# FPGA.net
KiCad netlist of a schematic drawn in Altium Designer
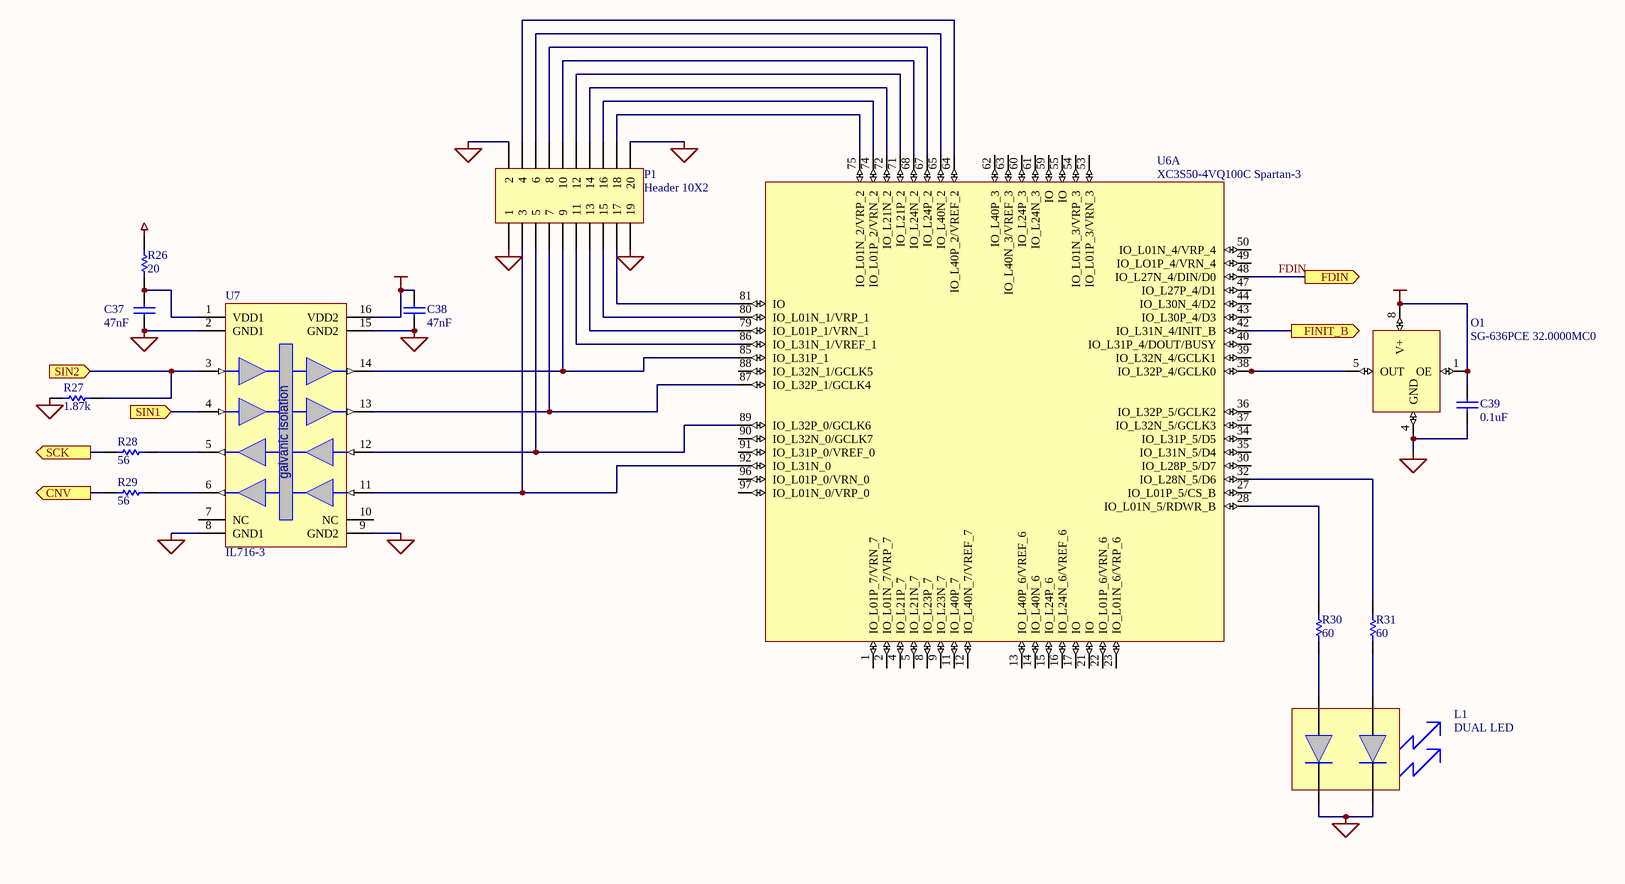
[diagram p0: FPGA.SCHDOC]

(export (version "E")
  (design (tool "Eeschema 10.0.6"))
  (components
    (comp (ref "C37")
      (value "47nF")
      (footprint "CC1608-0603")
      (description "Capacitor")
      (fields
        (field (name "MANUFACTURER") "Generic Components")
        (field (name "Comment") "Cap")
        (field (name "PUBLISHER") "Altium Limited")
      )
      (libsource (lib "Miscellaneous Devices") (part "Cap"))
    )
    (comp (ref "C38")
      (value "47nF")
      (footprint "CC1608-0603")
      (description "Capacitor")
      (fields
        (field (name "MANUFACTURER") "Generic Components")
        (field (name "Comment") "Cap")
        (field (name "PUBLISHER") "Altium Limited")
      )
      (libsource (lib "Miscellaneous Devices") (part "Cap"))
    )
    (comp (ref "C39")
      (value "0.1uF")
      (footprint "CC1608-0603")
      (description "Capacitor")
      (fields
        (field (name "MANUFACTURER") "Generic Components")
        (field (name "Comment") "Cap")
        (field (name "PUBLISHER") "Altium Limited")
      )
      (libsource (lib "Miscellaneous Devices") (part "Cap"))
    )
    (comp (ref "L1")
      (value "DUAL LED")
      (footprint "LUMEX DUAL RT-ANG LED")
      (libsource (lib "parts") (part "DUAL LED"))
    )
    (comp (ref "O1")
      (value "SG-636PCE 32.0000MC0")
      (footprint "SG636PCE")
      (description "Epson CMOS/TTL Oscillator")
      (libsource (lib "parts") (part "SG-636PCE"))
    )
    (comp (ref "P1")
      (value "Header 10X2")
      (footprint "HDR2X10")
      (description "Header, 10-Pin, Dual row")
      (fields (field (name "PUBLISHER") "Altium Limited"))
      (libsource (lib "Miscellaneous Connectors") (part "Header 10X2"))
    )
    (comp (ref "R26")
      (value "20")
      (footprint "CC1608-0603")
      (description "Resistor")
      (fields
        (field (name "MANUFACTURER") "Generic Components")
        (field (name "Comment") "Res1")
        (field (name "PUBLISHER") "Altium Limited")
      )
      (libsource (lib "Miscellaneous Devices") (part "Res1"))
    )
    (comp (ref "R27")
      (value "1.87k")
      (footprint "CC1608-0603")
      (description "Resistor")
      (fields
        (field (name "MANUFACTURER") "Generic Components")
        (field (name "Comment") "Res1")
        (field (name "PUBLISHER") "Altium Limited")
      )
      (libsource (lib "Miscellaneous Devices") (part "Res1"))
    )
    (comp (ref "R28")
      (value "56")
      (footprint "CC1608-0603")
      (description "Resistor")
      (fields
        (field (name "MANUFACTURER") "Generic Components")
        (field (name "Comment") "Res1")
        (field (name "PUBLISHER") "Altium Limited")
      )
      (libsource (lib "Miscellaneous Devices") (part "Res1"))
    )
    (comp (ref "R29")
      (value "56")
      (footprint "CC1608-0603")
      (description "Resistor")
      (fields
        (field (name "MANUFACTURER") "Generic Components")
        (field (name "Comment") "Res1")
        (field (name "PUBLISHER") "Altium Limited")
      )
      (libsource (lib "Miscellaneous Devices") (part "Res1"))
    )
    (comp (ref "R30")
      (value "60")
      (footprint "CC1608-0603")
      (description "Resistor")
      (fields
        (field (name "MANUFACTURER") "Generic Components")
        (field (name "Comment") "Res1")
        (field (name "PUBLISHER") "Altium Limited")
      )
      (libsource (lib "Miscellaneous Devices") (part "Res1"))
    )
    (comp (ref "R31")
      (value "60")
      (footprint "CC1608-0603")
      (description "Resistor")
      (fields
        (field (name "MANUFACTURER") "Generic Components")
        (field (name "Comment") "Res1")
        (field (name "PUBLISHER") "Altium Limited")
      )
      (libsource (lib "Miscellaneous Devices") (part "Res1"))
    )
    (comp (ref "U6")
      (value "XC3S50-4VQ100C Spartan-3")
      (footprint "Xilinx TQ100")
      (description "Xilinx Spartan-3 VQ100")
      (libsource (lib "parts") (part "XC3S50-4VQ100C"))
    )
    (comp (ref "U7")
      (value "IL716-3")
      (footprint "SO-G16/D10")
      (description "High speed digital coupler")
      (libsource (lib "parts") (part "IL716-3"))
    )
  )
  (nets
    (net (code "1") (name "/CNV") (class "Default")
      (node (ref "R29") (pin "1") (pinfunction "1_1") (pintype "passive"))
    )
    (net (code "2") (name "/FDIN") (class "Default")
      (node (ref "U6") (pin "48") (pinfunction "IO_L27N_4/DIN/D0_48") (pintype "bidirectional"))
    )
    (net (code "3") (name "/FINIT_B") (class "Default")
      (node (ref "U6") (pin "42") (pinfunction "IO_L31N_4/INIT_B_42") (pintype "bidirectional"))
    )
    (net (code "4") (name "/SCK") (class "Default")
      (node (ref "R28") (pin "1") (pinfunction "1_1") (pintype "passive"))
    )
    (net (code "5") (name "/SIN1") (class "Default")
      (node (ref "U7") (pin "4") (pinfunction "IN2_4") (pintype "input"))
    )
    (net (code "6") (name "/SIN2") (class "Default")
      (node (ref "R27") (pin "2") (pinfunction "2_2") (pintype "passive"))
      (node (ref "U7") (pin "3") (pinfunction "IN1_3") (pintype "input"))
    )
    (net (code "7") (name "AGND") (class "Default")
      (node (ref "C37") (pin "1") (pinfunction "1_1") (pintype "passive"))
      (node (ref "R27") (pin "1") (pinfunction "1_1") (pintype "passive"))
      (node (ref "U7") (pin "2") (pinfunction "GND1_2") (pintype "power_in"))
      (node (ref "U7") (pin "8") (pinfunction "GND1_8") (pintype "power_in"))
    )
    (net (code "8") (name "AVDD") (class "Default")
      (node (ref "R26") (pin "2") (pinfunction "2_2") (pintype "passive"))
    )
    (net (code "9") (name "GND") (class "Default")
      (node (ref "C38") (pin "1") (pinfunction "1_1") (pintype "passive"))
      (node (ref "C39") (pin "2") (pinfunction "2_2") (pintype "passive"))
      (node (ref "L1") (pin "2") (pinfunction "2_2") (pintype "passive"))
      (node (ref "L1") (pin "4") (pinfunction "C2_4") (pintype "passive"))
      (node (ref "O1") (pin "4") (pinfunction "GND_4") (pintype "bidirectional"))
      (node (ref "P1") (pin "1") (pinfunction "1_1") (pintype "passive"))
      (node (ref "P1") (pin "19") (pinfunction "19_19") (pintype "passive"))
      (node (ref "P1") (pin "2") (pinfunction "2_2") (pintype "passive"))
      (node (ref "P1") (pin "20") (pinfunction "20_20") (pintype "passive"))
      (node (ref "U7") (pin "15") (pinfunction "GND2_15") (pintype "power_in"))
      (node (ref "U7") (pin "9") (pinfunction "GND2_9") (pintype "power_in"))
    )
    (net (code "10") (name "Net-(L1-A1)") (class "Default")
      (node (ref "L1") (pin "1") (pinfunction "A1_1") (pintype "passive"))
      (node (ref "R30") (pin "2") (pinfunction "2_2") (pintype "passive"))
    )
    (net (code "11") (name "Net-(L1-A2)") (class "Default")
      (node (ref "L1") (pin "3") (pinfunction "A2_3") (pintype "passive"))
      (node (ref "R31") (pin "2") (pinfunction "2_2") (pintype "passive"))
    )
    (net (code "12") (name "Net-(O1-OUT)") (class "Default")
      (node (ref "O1") (pin "5") (pinfunction "OUT_5") (pintype "bidirectional"))
      (node (ref "U6") (pin "38") (pinfunction "IO_L32P_4/GCLK0_38") (pintype "bidirectional"))
    )
    (net (code "13") (name "Net-(P1-Pad17)") (class "Default")
      (node (ref "P1") (pin "17") (pinfunction "17_17") (pintype "passive"))
      (node (ref "U6") (pin "81") (pinfunction "IO_81") (pintype "bidirectional"))
    )
    (net (code "14") (name "Net-(U6A-IO_L01N_1{slash}VRP_1)") (class "Default")
      (node (ref "P1") (pin "15") (pinfunction "15_15") (pintype "passive"))
      (node (ref "U6") (pin "80") (pinfunction "IO_L01N_1/VRP_1_80") (pintype "bidirectional"))
    )
    (net (code "15") (name "Net-(U6A-IO_L01N_2{slash}VRP_2)") (class "Default")
      (node (ref "P1") (pin "18") (pinfunction "18_18") (pintype "passive"))
      (node (ref "U6") (pin "75") (pinfunction "IO_L01N_2/VRP_2_75") (pintype "bidirectional"))
    )
    (net (code "16") (name "Net-(U6A-IO_L01N_5{slash}RDWR_B)") (class "Default")
      (node (ref "R30") (pin "1") (pinfunction "1_1") (pintype "passive"))
      (node (ref "U6") (pin "28") (pinfunction "IO_L01N_5/RDWR_B_28") (pintype "bidirectional"))
    )
    (net (code "17") (name "Net-(U6A-IO_L01P_1{slash}VRN_1)") (class "Default")
      (node (ref "P1") (pin "13") (pinfunction "13_13") (pintype "passive"))
      (node (ref "U6") (pin "79") (pinfunction "IO_L01P_1/VRN_1_79") (pintype "bidirectional"))
    )
    (net (code "18") (name "Net-(U6A-IO_L01P_2{slash}VRN_2)") (class "Default")
      (node (ref "P1") (pin "16") (pinfunction "16_16") (pintype "passive"))
      (node (ref "U6") (pin "74") (pinfunction "IO_L01P_2/VRN_2_74") (pintype "bidirectional"))
    )
    (net (code "19") (name "Net-(U6A-IO_L21N_2)") (class "Default")
      (node (ref "P1") (pin "14") (pinfunction "14_14") (pintype "passive"))
      (node (ref "U6") (pin "72") (pinfunction "IO_L21N_2_72") (pintype "bidirectional"))
    )
    (net (code "20") (name "Net-(U6A-IO_L21P_2)") (class "Default")
      (node (ref "P1") (pin "12") (pinfunction "12_12") (pintype "passive"))
      (node (ref "U6") (pin "71") (pinfunction "IO_L21P_2_71") (pintype "bidirectional"))
    )
    (net (code "21") (name "Net-(U6A-IO_L24N_2)") (class "Default")
      (node (ref "P1") (pin "10") (pinfunction "10_10") (pintype "passive"))
      (node (ref "U6") (pin "68") (pinfunction "IO_L24N_2_68") (pintype "bidirectional"))
    )
    (net (code "22") (name "Net-(U6A-IO_L24P_2)") (class "Default")
      (node (ref "P1") (pin "8") (pinfunction "8_8") (pintype "passive"))
      (node (ref "U6") (pin "67") (pinfunction "IO_L24P_2_67") (pintype "bidirectional"))
    )
    (net (code "23") (name "Net-(U6A-IO_L28N_5{slash}D6)") (class "Default")
      (node (ref "R31") (pin "1") (pinfunction "1_1") (pintype "passive"))
      (node (ref "U6") (pin "32") (pinfunction "IO_L28N_5/D6_32") (pintype "bidirectional"))
    )
    (net (code "24") (name "Net-(U6A-IO_L31N_0)") (class "Default")
      (node (ref "P1") (pin "3") (pinfunction "3_3") (pintype "passive"))
      (node (ref "U6") (pin "92") (pinfunction "IO_L31N_0_92") (pintype "bidirectional"))
      (node (ref "U7") (pin "11") (pinfunction "IN4_11") (pintype "input"))
    )
    (net (code "25") (name "Net-(U6A-IO_L31N_1{slash}VREF_1)") (class "Default")
      (node (ref "P1") (pin "11") (pinfunction "11_11") (pintype "passive"))
      (node (ref "U6") (pin "86") (pinfunction "IO_L31N_1/VREF_1_86") (pintype "bidirectional"))
    )
    (net (code "26") (name "Net-(U6A-IO_L31P_1)") (class "Default")
      (node (ref "P1") (pin "9") (pinfunction "9_9") (pintype "passive"))
      (node (ref "U6") (pin "85") (pinfunction "IO_L31P_1_85") (pintype "bidirectional"))
      (node (ref "U7") (pin "14") (pinfunction "OUT1_14") (pintype "output"))
    )
    (net (code "27") (name "Net-(U6A-IO_L32P_0{slash}GCLK6)") (class "Default")
      (node (ref "P1") (pin "5") (pinfunction "5_5") (pintype "passive"))
      (node (ref "U6") (pin "89") (pinfunction "IO_L32P_0/GCLK6_89") (pintype "bidirectional"))
      (node (ref "U7") (pin "12") (pinfunction "IN3_12") (pintype "input"))
    )
    (net (code "28") (name "Net-(U6A-IO_L32P_1{slash}GCLK4)") (class "Default")
      (node (ref "P1") (pin "7") (pinfunction "7_7") (pintype "passive"))
      (node (ref "U6") (pin "87") (pinfunction "IO_L32P_1/GCLK4_87") (pintype "bidirectional"))
      (node (ref "U7") (pin "13") (pinfunction "OUT2_13") (pintype "output"))
    )
    (net (code "29") (name "Net-(U6A-IO_L40N_2)") (class "Default")
      (node (ref "P1") (pin "6") (pinfunction "6_6") (pintype "passive"))
      (node (ref "U6") (pin "65") (pinfunction "IO_L40N_2_65") (pintype "bidirectional"))
    )
    (net (code "30") (name "Net-(U6A-IO_L40P_2{slash}VREF_2)") (class "Default")
      (node (ref "P1") (pin "4") (pinfunction "4_4") (pintype "passive"))
      (node (ref "U6") (pin "64") (pinfunction "IO_L40P_2/VREF_2_64") (pintype "bidirectional"))
    )
    (net (code "31") (name "Net-(U7-OUT3)") (class "Default")
      (node (ref "R28") (pin "2") (pinfunction "2_2") (pintype "passive"))
      (node (ref "U7") (pin "5") (pinfunction "OUT3_5") (pintype "output"))
    )
    (net (code "32") (name "Net-(U7-OUT4)") (class "Default")
      (node (ref "R29") (pin "2") (pinfunction "2_2") (pintype "passive"))
      (node (ref "U7") (pin "6") (pinfunction "OUT4_6") (pintype "output"))
    )
    (net (code "33") (name "Net-(U7-VDD1)") (class "Default")
      (node (ref "C37") (pin "2") (pinfunction "2_2") (pintype "passive"))
      (node (ref "R26") (pin "1") (pinfunction "1_1") (pintype "passive"))
      (node (ref "U7") (pin "1") (pinfunction "VDD1_1") (pintype "power_in"))
    )
    (net (code "34") (name "VCC") (class "Default")
      (node (ref "C38") (pin "2") (pinfunction "2_2") (pintype "passive"))
      (node (ref "C39") (pin "1") (pinfunction "1_1") (pintype "passive"))
      (node (ref "O1") (pin "1") (pinfunction "OE_1") (pintype "bidirectional"))
      (node (ref "O1") (pin "8") (pinfunction "V+_8") (pintype "bidirectional"))
      (node (ref "U7") (pin "16") (pinfunction "VDD2_16") (pintype "power_in"))
    )
    (net (code "35") (name "unconnected-(U6A-IO-Pad17)") (class "Default")
      (node (ref "U6") (pin "17") (pinfunction "IO_17") (pintype "bidirectional"))
    )
    (net (code "36") (name "unconnected-(U6A-IO-Pad21)") (class "Default")
      (node (ref "U6") (pin "21") (pinfunction "IO_21") (pintype "bidirectional"))
    )
    (net (code "37") (name "unconnected-(U6A-IO-Pad55)") (class "Default")
      (node (ref "U6") (pin "55") (pinfunction "IO_55") (pintype "bidirectional"))
    )
    (net (code "38") (name "unconnected-(U6A-IO-Pad59)") (class "Default")
      (node (ref "U6") (pin "59") (pinfunction "IO_59") (pintype "bidirectional"))
    )
    (net (code "39") (name "unconnected-(U6A-IO_L01N_0{slash}VRP_0-Pad97)") (class "Default")
      (node (ref "U6") (pin "97") (pinfunction "IO_L01N_0/VRP_0_97") (pintype "bidirectional"))
    )
    (net (code "40") (name "unconnected-(U6A-IO_L01N_3{slash}VRP_3-Pad54)") (class "Default")
      (node (ref "U6") (pin "54") (pinfunction "IO_L01N_3/VRP_3_54") (pintype "bidirectional"))
    )
    (net (code "41") (name "unconnected-(U6A-IO_L01N_4{slash}VRP_4-Pad50)") (class "Default")
      (node (ref "U6") (pin "50") (pinfunction "IO_L01N_4/VRP_4_50") (pintype "bidirectional"))
    )
    (net (code "42") (name "unconnected-(U6A-IO_L01N_6{slash}VRP_6-Pad23)") (class "Default")
      (node (ref "U6") (pin "23") (pinfunction "IO_L01N_6/VRP_6_23") (pintype "bidirectional"))
    )
    (net (code "43") (name "unconnected-(U6A-IO_L01N_7{slash}VRP_7-Pad2)") (class "Default")
      (node (ref "U6") (pin "2") (pinfunction "IO_L01N_7/VRP_7_2") (pintype "bidirectional"))
    )
    (net (code "44") (name "unconnected-(U6A-IO_L01P_0{slash}VRN_0-Pad96)") (class "Default")
      (node (ref "U6") (pin "96") (pinfunction "IO_L01P_0/VRN_0_96") (pintype "bidirectional"))
    )
    (net (code "45") (name "unconnected-(U6A-IO_L01P_3{slash}VRN_3-Pad53)") (class "Default")
      (node (ref "U6") (pin "53") (pinfunction "IO_L01P_3/VRN_3_53") (pintype "bidirectional"))
    )
    (net (code "46") (name "unconnected-(U6A-IO_L01P_5{slash}CS_B-Pad27)") (class "Default")
      (node (ref "U6") (pin "27") (pinfunction "IO_L01P_5/CS_B_27") (pintype "bidirectional"))
    )
    (net (code "47") (name "unconnected-(U6A-IO_L01P_6{slash}VRN_6-Pad22)") (class "Default")
      (node (ref "U6") (pin "22") (pinfunction "IO_L01P_6/VRN_6_22") (pintype "bidirectional"))
    )
    (net (code "48") (name "unconnected-(U6A-IO_L01P_7{slash}VRN_7-Pad1)") (class "Default")
      (node (ref "U6") (pin "1") (pinfunction "IO_L01P_7/VRN_7_1") (pintype "bidirectional"))
    )
    (net (code "49") (name "unconnected-(U6A-IO_L21N_7-Pad5)") (class "Default")
      (node (ref "U6") (pin "5") (pinfunction "IO_L21N_7_5") (pintype "bidirectional"))
    )
    (net (code "50") (name "unconnected-(U6A-IO_L21P_7-Pad4)") (class "Default")
      (node (ref "U6") (pin "4") (pinfunction "IO_L21P_7_4") (pintype "bidirectional"))
    )
    (net (code "51") (name "unconnected-(U6A-IO_L23N_7-Pad9)") (class "Default")
      (node (ref "U6") (pin "9") (pinfunction "IO_L23N_7_9") (pintype "bidirectional"))
    )
    (net (code "52") (name "unconnected-(U6A-IO_L23P_7-Pad8)") (class "Default")
      (node (ref "U6") (pin "8") (pinfunction "IO_L23P_7_8") (pintype "bidirectional"))
    )
    (net (code "53") (name "unconnected-(U6A-IO_L24N_3-Pad61)") (class "Default")
      (node (ref "U6") (pin "61") (pinfunction "IO_L24N_3_61") (pintype "bidirectional"))
    )
    (net (code "54") (name "unconnected-(U6A-IO_L24N_6{slash}VREF_6-Pad16)") (class "Default")
      (node (ref "U6") (pin "16") (pinfunction "IO_L24N_6/VREF_6_16") (pintype "bidirectional"))
    )
    (net (code "55") (name "unconnected-(U6A-IO_L24P_3-Pad60)") (class "Default")
      (node (ref "U6") (pin "60") (pinfunction "IO_L24P_3_60") (pintype "bidirectional"))
    )
    (net (code "56") (name "unconnected-(U6A-IO_L24P_6-Pad15)") (class "Default")
      (node (ref "U6") (pin "15") (pinfunction "IO_L24P_6_15") (pintype "bidirectional"))
    )
    (net (code "57") (name "unconnected-(U6A-IO_L27P_4{slash}D1-Pad47)") (class "Default")
      (node (ref "U6") (pin "47") (pinfunction "IO_L27P_4/D1_47") (pintype "bidirectional"))
    )
    (net (code "58") (name "unconnected-(U6A-IO_L28P_5{slash}D7-Pad30)") (class "Default")
      (node (ref "U6") (pin "30") (pinfunction "IO_L28P_5/D7_30") (pintype "bidirectional"))
    )
    (net (code "59") (name "unconnected-(U6A-IO_L30N_4{slash}D2-Pad44)") (class "Default")
      (node (ref "U6") (pin "44") (pinfunction "IO_L30N_4/D2_44") (pintype "bidirectional"))
    )
    (net (code "60") (name "unconnected-(U6A-IO_L30P_4{slash}D3-Pad43)") (class "Default")
      (node (ref "U6") (pin "43") (pinfunction "IO_L30P_4/D3_43") (pintype "bidirectional"))
    )
    (net (code "61") (name "unconnected-(U6A-IO_L31N_5{slash}D4-Pad35)") (class "Default")
      (node (ref "U6") (pin "35") (pinfunction "IO_L31N_5/D4_35") (pintype "bidirectional"))
    )
    (net (code "62") (name "unconnected-(U6A-IO_L31P_0{slash}VREF_0-Pad91)") (class "Default")
      (node (ref "U6") (pin "91") (pinfunction "IO_L31P_0/VREF_0_91") (pintype "bidirectional"))
    )
    (net (code "63") (name "unconnected-(U6A-IO_L31P_4{slash}DOUT{slash}BUSY-Pad40)") (class "Default")
      (node (ref "U6") (pin "40") (pinfunction "IO_L31P_4/DOUT/BUSY_40") (pintype "bidirectional"))
    )
    (net (code "64") (name "unconnected-(U6A-IO_L31P_5{slash}D5-Pad34)") (class "Default")
      (node (ref "U6") (pin "34") (pinfunction "IO_L31P_5/D5_34") (pintype "bidirectional"))
    )
    (net (code "65") (name "unconnected-(U6A-IO_L32N_0{slash}GCLK7-Pad90)") (class "Default")
      (node (ref "U6") (pin "90") (pinfunction "IO_L32N_0/GCLK7_90") (pintype "bidirectional"))
    )
    (net (code "66") (name "unconnected-(U6A-IO_L32N_1{slash}GCLK5-Pad88)") (class "Default")
      (node (ref "U6") (pin "88") (pinfunction "IO_L32N_1/GCLK5_88") (pintype "bidirectional"))
    )
    (net (code "67") (name "unconnected-(U6A-IO_L32N_4{slash}GCLK1-Pad39)") (class "Default")
      (node (ref "U6") (pin "39") (pinfunction "IO_L32N_4/GCLK1_39") (pintype "bidirectional"))
    )
    (net (code "68") (name "unconnected-(U6A-IO_L32N_5{slash}GCLK3-Pad37)") (class "Default")
      (node (ref "U6") (pin "37") (pinfunction "IO_L32N_5/GCLK3_37") (pintype "bidirectional"))
    )
    (net (code "69") (name "unconnected-(U6A-IO_L32P_5{slash}GCLK2-Pad36)") (class "Default")
      (node (ref "U6") (pin "36") (pinfunction "IO_L32P_5/GCLK2_36") (pintype "bidirectional"))
    )
    (net (code "70") (name "unconnected-(U6A-IO_L40N_3{slash}VREF_3-Pad63)") (class "Default")
      (node (ref "U6") (pin "63") (pinfunction "IO_L40N_3/VREF_3_63") (pintype "bidirectional"))
    )
    (net (code "71") (name "unconnected-(U6A-IO_L40N_6-Pad14)") (class "Default")
      (node (ref "U6") (pin "14") (pinfunction "IO_L40N_6_14") (pintype "bidirectional"))
    )
    (net (code "72") (name "unconnected-(U6A-IO_L40N_7{slash}VREF_7-Pad12)") (class "Default")
      (node (ref "U6") (pin "12") (pinfunction "IO_L40N_7/VREF_7_12") (pintype "bidirectional"))
    )
    (net (code "73") (name "unconnected-(U6A-IO_L40P_3-Pad62)") (class "Default")
      (node (ref "U6") (pin "62") (pinfunction "IO_L40P_3_62") (pintype "bidirectional"))
    )
    (net (code "74") (name "unconnected-(U6A-IO_L40P_6{slash}VREF_6-Pad13)") (class "Default")
      (node (ref "U6") (pin "13") (pinfunction "IO_L40P_6/VREF_6_13") (pintype "bidirectional"))
    )
    (net (code "75") (name "unconnected-(U6A-IO_L40P_7-Pad11)") (class "Default")
      (node (ref "U6") (pin "11") (pinfunction "IO_L40P_7_11") (pintype "bidirectional"))
    )
    (net (code "76") (name "unconnected-(U6A-IO_LO1P_4{slash}VRN_4-Pad49)") (class "Default")
      (node (ref "U6") (pin "49") (pinfunction "IO_LO1P_4/VRN_4_49") (pintype "bidirectional"))
    )
    (net (code "77") (name "unconnected-(U7-NC-Pad7)") (class "Default")
      (node (ref "U7") (pin "7") (pinfunction "NC_7") (pintype "passive"))
    )
    (net (code "78") (name "unconnected-(U7-NC-Pad10)") (class "Default")
      (node (ref "U7") (pin "10") (pinfunction "NC_10") (pintype "passive"))
    )
  )
)
